# mosfet-fin.net
KiCad netlist of a schematic drawn in EAGLE
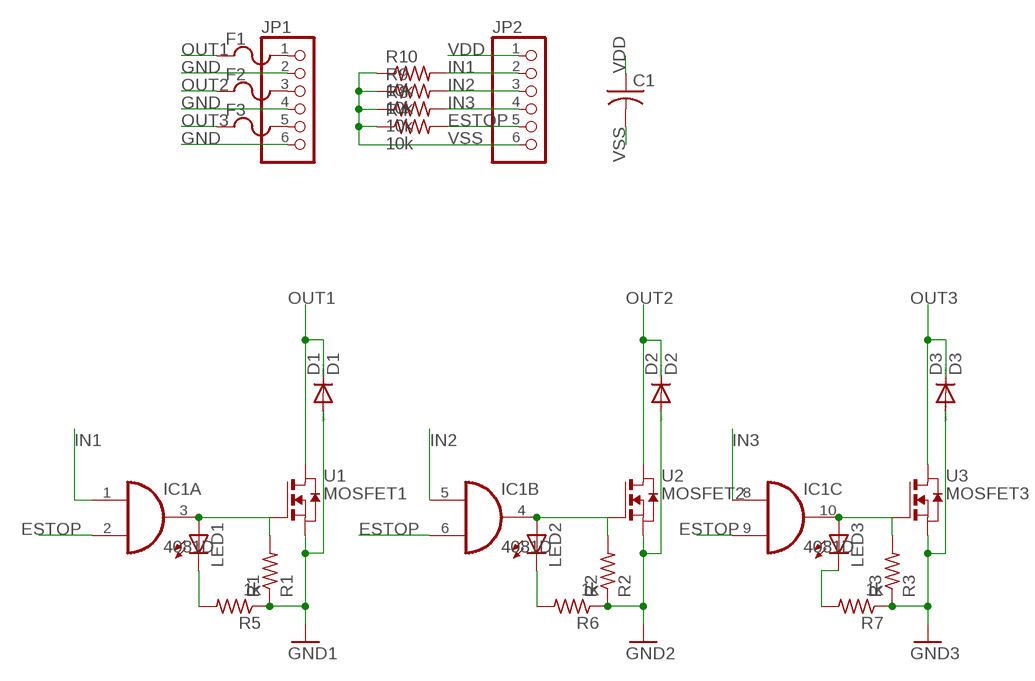
[diagram p0: schematic, sheet 1]

(export (version "E")
  (design (tool "Eeschema 10.0.6"))
  (components
    (comp (ref "C1")
      (value "C-USC0603")
      (footprint "eagle-import:C0603")
      (libsource (lib "eagle-import") (part "C-USC0603"))
    )
    (comp (ref "D1")
      (value "D1")
      (footprint "eagle-import:DO41-10")
      (libsource (lib "eagle-import") (part "1N4004"))
    )
    (comp (ref "D2")
      (value "D2")
      (footprint "eagle-import:DO41-10")
      (libsource (lib "eagle-import") (part "1N4004"))
    )
    (comp (ref "D3")
      (value "D3")
      (footprint "eagle-import:DO41-10")
      (libsource (lib "eagle-import") (part "1N4004"))
    )
    (comp (ref "F1")
      (value "POLYFUSE")
      (footprint "eagle-import:1206")
      (libsource (lib "eagle-import") (part "POLYFUSE"))
    )
    (comp (ref "F2")
      (value "POLYFUSE")
      (footprint "eagle-import:1206")
      (libsource (lib "eagle-import") (part "POLYFUSE"))
    )
    (comp (ref "F3")
      (value "POLYFUSE")
      (footprint "eagle-import:1206")
      (libsource (lib "eagle-import") (part "POLYFUSE"))
    )
    (comp (ref "IC1")
      (value "4081D")
      (footprint "eagle-import:SO14")
      (libsource (lib "eagle-import") (part "4081D"))
    )
    (comp (ref "JP1")
      (value "PINHD-1X6")
      (footprint "eagle-import:1X06")
      (libsource (lib "eagle-import") (part "PINHD-1X6"))
    )
    (comp (ref "JP2")
      (value "PINHD-1X6")
      (footprint "eagle-import:1X06")
      (libsource (lib "eagle-import") (part "PINHD-1X6"))
    )
    (comp (ref "LED1")
      (value "LEDCHIPLED-0603-TTW")
      (footprint "eagle-import:CHIPLED-0603-TTW")
      (libsource (lib "eagle-import") (part "LEDCHIPLED-0603-TTW"))
    )
    (comp (ref "LED2")
      (value "LEDCHIPLED-0603-TTW")
      (footprint "eagle-import:CHIPLED-0603-TTW")
      (libsource (lib "eagle-import") (part "LEDCHIPLED-0603-TTW"))
    )
    (comp (ref "LED3")
      (value "LEDCHIPLED-0603-TTW")
      (footprint "eagle-import:CHIPLED-0603-TTW")
      (libsource (lib "eagle-import") (part "LEDCHIPLED-0603-TTW"))
    )
    (comp (ref "R1")
      (value "R1")
      (footprint "eagle-import:R0603")
      (libsource (lib "eagle-import") (part "resistor_R-US_R0603"))
    )
    (comp (ref "R2")
      (value "R2")
      (footprint "eagle-import:R0603")
      (libsource (lib "eagle-import") (part "resistor_R-US_R0603"))
    )
    (comp (ref "R3")
      (value "R3")
      (footprint "eagle-import:R0603")
      (libsource (lib "eagle-import") (part "resistor_R-US_R0603"))
    )
    (comp (ref "R4")
      (value "10k")
      (footprint "eagle-import:R0603")
      (libsource (lib "eagle-import") (part "R-US_R0603"))
    )
    (comp (ref "R5")
      (value "1k")
      (footprint "eagle-import:R0603")
      (libsource (lib "eagle-import") (part "resistor_R-US_R0603"))
    )
    (comp (ref "R6")
      (value "1k")
      (footprint "eagle-import:R0603")
      (libsource (lib "eagle-import") (part "resistor_R-US_R0603"))
    )
    (comp (ref "R7")
      (value "1k")
      (footprint "eagle-import:R0603")
      (libsource (lib "eagle-import") (part "resistor_R-US_R0603"))
    )
    (comp (ref "R8")
      (value "10k")
      (footprint "eagle-import:R0603")
      (libsource (lib "eagle-import") (part "R-US_R0603"))
    )
    (comp (ref "R9")
      (value "10k")
      (footprint "eagle-import:R0603")
      (libsource (lib "eagle-import") (part "R-US_R0603"))
    )
    (comp (ref "R10")
      (value "10k")
      (footprint "eagle-import:R0603")
      (libsource (lib "eagle-import") (part "R-US_R0603"))
    )
    (comp (ref "U1")
      (value "MOSFET1")
      (footprint "eagle-import:MOSFET")
      (libsource (lib "eagle-import") (part "MOSFET"))
    )
    (comp (ref "U2")
      (value "MOSFET2")
      (footprint "eagle-import:MOSFET")
      (libsource (lib "eagle-import") (part "MOSFET"))
    )
    (comp (ref "U3")
      (value "MOSFET3")
      (footprint "eagle-import:MOSFET")
      (libsource (lib "eagle-import") (part "MOSFET"))
    )
  )
  (nets
    (net (code "1") (name "/ESTOP") (class "Default")
      (node (ref "IC1") (pin "2") (pinfunction "I1_2") (pintype "input"))
      (node (ref "IC1") (pin "6") (pinfunction "I1_6") (pintype "input"))
      (node (ref "IC1") (pin "9") (pinfunction "I1_9") (pintype "input"))
      (node (ref "JP2") (pin "5") (pinfunction "5_5") (pintype "passive"))
      (node (ref "R4") (pin "2") (pinfunction "2_2") (pintype "passive"))
    )
    (net (code "2") (name "/IN1") (class "Default")
      (node (ref "IC1") (pin "1") (pinfunction "I0_1") (pintype "input"))
      (node (ref "JP2") (pin "2") (pinfunction "2_2") (pintype "passive"))
      (node (ref "R10") (pin "2") (pinfunction "2_2") (pintype "passive"))
    )
    (net (code "3") (name "/IN2") (class "Default")
      (node (ref "IC1") (pin "5") (pinfunction "I0_5") (pintype "input"))
      (node (ref "JP2") (pin "3") (pinfunction "3_3") (pintype "passive"))
      (node (ref "R9") (pin "2") (pinfunction "2_2") (pintype "passive"))
    )
    (net (code "4") (name "/IN3") (class "Default")
      (node (ref "IC1") (pin "8") (pinfunction "I0_8") (pintype "input"))
      (node (ref "JP2") (pin "4") (pinfunction "4_4") (pintype "passive"))
      (node (ref "R8") (pin "2") (pinfunction "2_2") (pintype "passive"))
    )
    (net (code "5") (name "/OUT1") (class "Default")
      (node (ref "D1") (pin "C") (pinfunction "C_C") (pintype "passive"))
      (node (ref "F1") (pin "1") (pinfunction "1_1") (pintype "passive"))
      (node (ref "U1") (pin "P$2") (pinfunction "D_P$2") (pintype "passive"))
    )
    (net (code "6") (name "/OUT2") (class "Default")
      (node (ref "D2") (pin "C") (pinfunction "C_C") (pintype "passive"))
      (node (ref "F2") (pin "1") (pinfunction "1_1") (pintype "passive"))
      (node (ref "U2") (pin "P$2") (pinfunction "D_P$2") (pintype "passive"))
    )
    (net (code "7") (name "/OUT3") (class "Default")
      (node (ref "D3") (pin "C") (pinfunction "C_C") (pintype "passive"))
      (node (ref "F3") (pin "1") (pinfunction "1_1") (pintype "passive"))
      (node (ref "U3") (pin "P$2") (pinfunction "D_P$2") (pintype "passive"))
    )
    (net (code "8") (name "/VDD") (class "Default")
      (node (ref "C1") (pin "1") (pinfunction "1_1") (pintype "passive"))
      (node (ref "JP2") (pin "1") (pinfunction "1_1") (pintype "passive"))
    )
    (net (code "9") (name "/VSS") (class "Default")
      (node (ref "C1") (pin "2") (pinfunction "2_2") (pintype "passive"))
      (node (ref "JP2") (pin "6") (pinfunction "6_6") (pintype "passive"))
      (node (ref "R10") (pin "1") (pinfunction "1_1") (pintype "passive"))
      (node (ref "R4") (pin "1") (pinfunction "1_1") (pintype "passive"))
      (node (ref "R8") (pin "1") (pinfunction "1_1") (pintype "passive"))
      (node (ref "R9") (pin "1") (pinfunction "1_1") (pintype "passive"))
    )
    (net (code "10") (name "GND1") (class "Default")
      (node (ref "D1") (pin "A") (pinfunction "A_A") (pintype "passive"))
      (node (ref "D2") (pin "A") (pinfunction "A_A") (pintype "passive"))
      (node (ref "D3") (pin "A") (pinfunction "A_A") (pintype "passive"))
      (node (ref "JP1") (pin "2") (pinfunction "2_2") (pintype "passive"))
      (node (ref "JP1") (pin "4") (pinfunction "4_4") (pintype "passive"))
      (node (ref "JP1") (pin "6") (pinfunction "6_6") (pintype "passive"))
      (node (ref "R1") (pin "1") (pinfunction "1_1") (pintype "passive"))
      (node (ref "R2") (pin "1") (pinfunction "1_1") (pintype "passive"))
      (node (ref "R3") (pin "1") (pinfunction "1_1") (pintype "passive"))
      (node (ref "R5") (pin "1") (pinfunction "1_1") (pintype "passive"))
      (node (ref "R6") (pin "1") (pinfunction "1_1") (pintype "passive"))
      (node (ref "R7") (pin "1") (pinfunction "1_1") (pintype "passive"))
      (node (ref "U1") (pin "P$3") (pinfunction "S_P$3") (pintype "passive"))
      (node (ref "U2") (pin "P$3") (pinfunction "S_P$3") (pintype "passive"))
      (node (ref "U3") (pin "P$3") (pinfunction "S_P$3") (pintype "passive"))
    )
    (net (code "11") (name "Net-(F1-Pad2)") (class "Default")
      (node (ref "F1") (pin "2") (pinfunction "2_2") (pintype "passive"))
      (node (ref "JP1") (pin "1") (pinfunction "1_1") (pintype "passive"))
    )
    (net (code "12") (name "Net-(F2-Pad2)") (class "Default")
      (node (ref "F2") (pin "2") (pinfunction "2_2") (pintype "passive"))
      (node (ref "JP1") (pin "3") (pinfunction "3_3") (pintype "passive"))
    )
    (net (code "13") (name "Net-(F3-Pad2)") (class "Default")
      (node (ref "F3") (pin "2") (pinfunction "2_2") (pintype "passive"))
      (node (ref "JP1") (pin "5") (pinfunction "5_5") (pintype "passive"))
    )
    (net (code "14") (name "Net-(IC1A-O)") (class "Default")
      (node (ref "IC1") (pin "3") (pinfunction "O_3") (pintype "output"))
      (node (ref "LED1") (pin "A@1") (pinfunction "A_A@1") (pintype "passive"))
      (node (ref "R1") (pin "2") (pinfunction "2_2") (pintype "passive"))
      (node (ref "U1") (pin "P$1") (pinfunction "G_P$1") (pintype "passive"))
    )
    (net (code "15") (name "Net-(IC1B-O)") (class "Default")
      (node (ref "IC1") (pin "4") (pinfunction "O_4") (pintype "output"))
      (node (ref "LED2") (pin "A@1") (pinfunction "A_A@1") (pintype "passive"))
      (node (ref "R2") (pin "2") (pinfunction "2_2") (pintype "passive"))
      (node (ref "U2") (pin "P$1") (pinfunction "G_P$1") (pintype "passive"))
    )
    (net (code "16") (name "Net-(IC1C-O)") (class "Default")
      (node (ref "IC1") (pin "10") (pinfunction "O_10") (pintype "output"))
      (node (ref "LED3") (pin "A@1") (pinfunction "A_A@1") (pintype "passive"))
      (node (ref "R3") (pin "2") (pinfunction "2_2") (pintype "passive"))
      (node (ref "U3") (pin "P$1") (pinfunction "G_P$1") (pintype "passive"))
    )
    (net (code "17") (name "Net-(LED1-C)") (class "Default")
      (node (ref "LED1") (pin "C@1") (pinfunction "C_C@1") (pintype "passive"))
      (node (ref "R5") (pin "2") (pinfunction "2_2") (pintype "passive"))
    )
    (net (code "18") (name "Net-(LED2-C)") (class "Default")
      (node (ref "LED2") (pin "C@1") (pinfunction "C_C@1") (pintype "passive"))
      (node (ref "R6") (pin "2") (pinfunction "2_2") (pintype "passive"))
    )
    (net (code "19") (name "Net-(LED3-C)") (class "Default")
      (node (ref "LED3") (pin "C@1") (pinfunction "C_C@1") (pintype "passive"))
      (node (ref "R7") (pin "2") (pinfunction "2_2") (pintype "passive"))
    )
  )
)
